# M611B.net
KiCad netlist of a schematic drawn in EAGLE
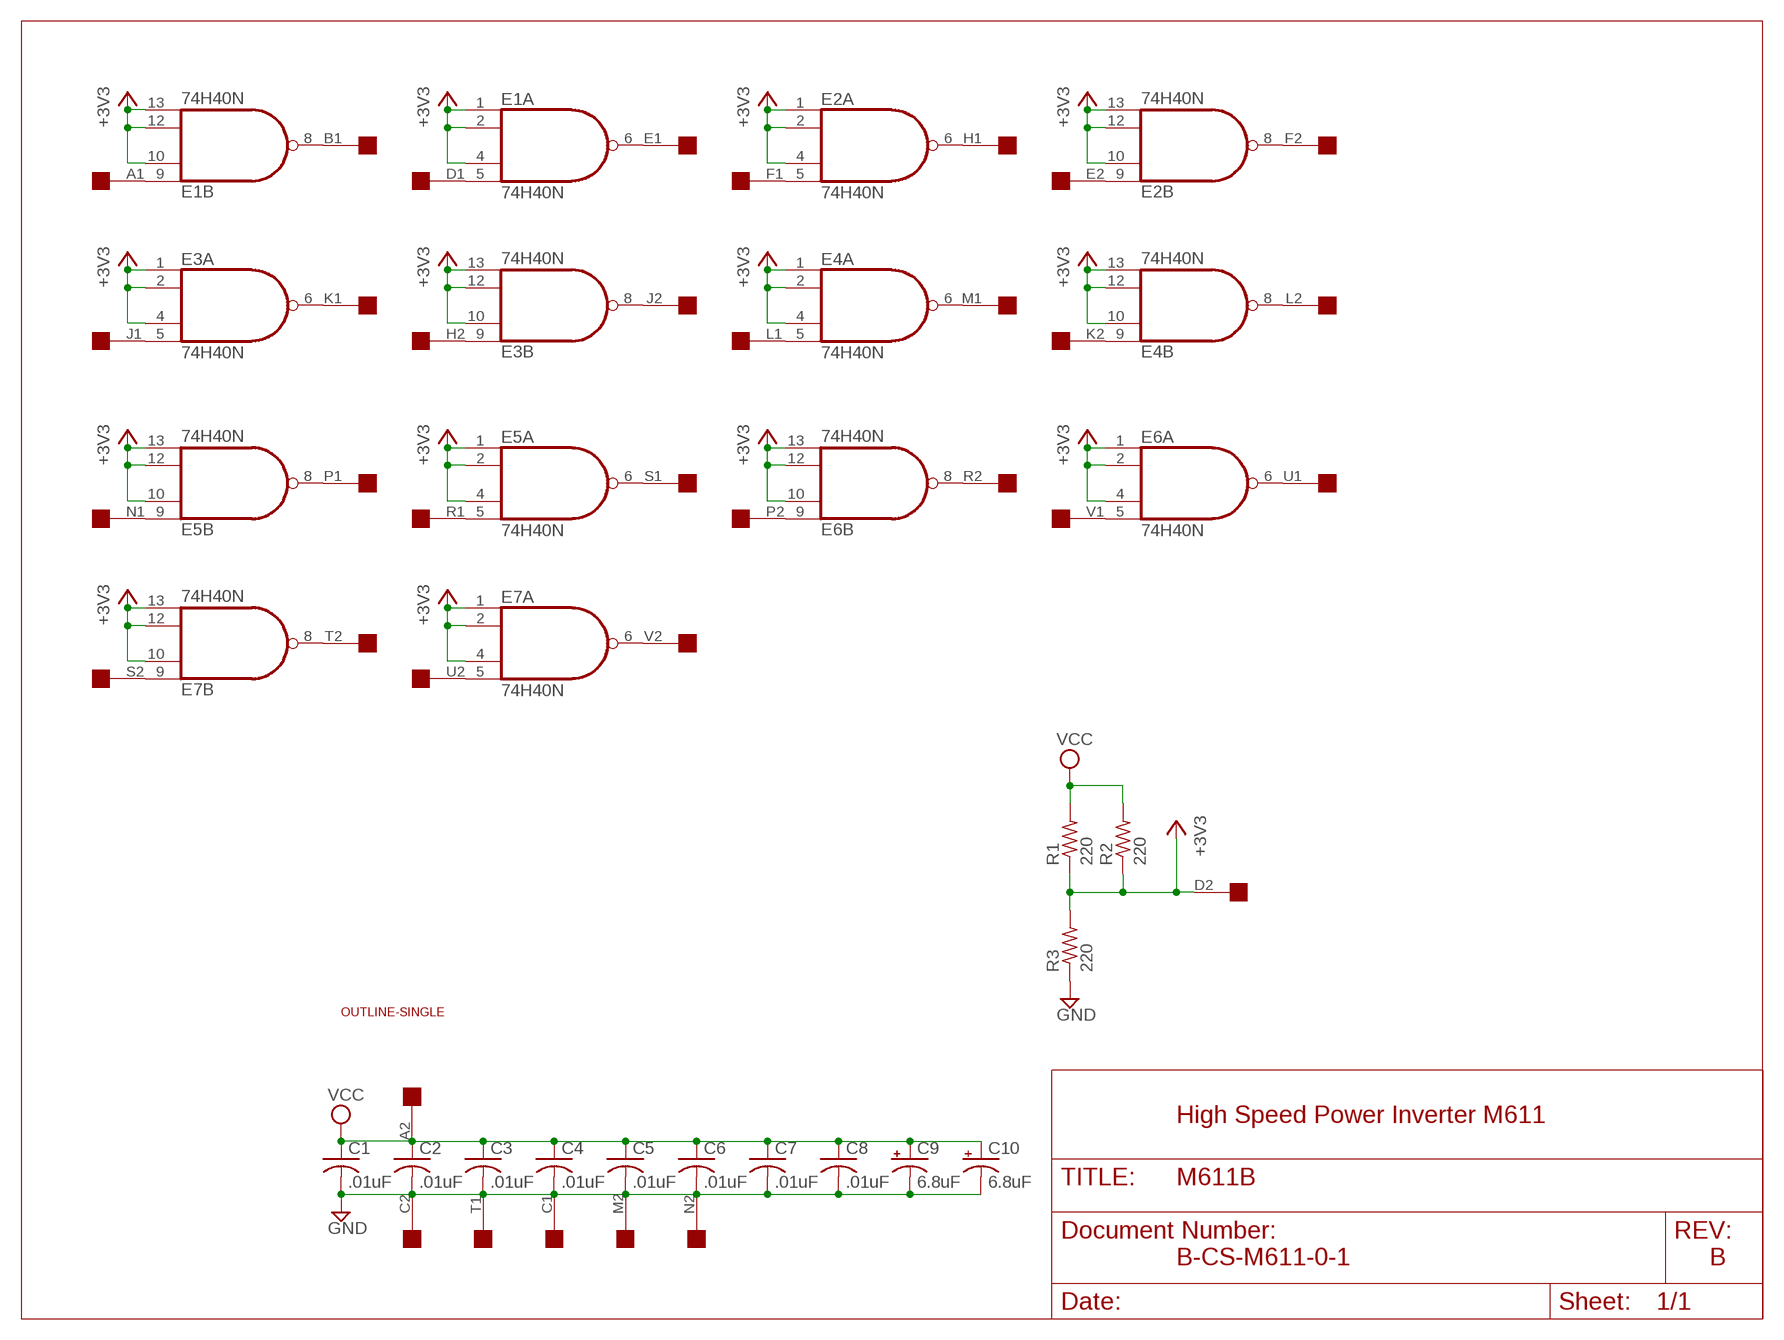
[diagram p0: schematic, sheet 1]

(export (version "E")
  (design (tool "Eeschema 10.0.6"))
  (components
    (comp (ref "C1")
      (value ".01uF")
      (footprint "eagle-import:C050-025X075")
      (libsource (lib "eagle-import") (part "C-US050-025X075"))
    )
    (comp (ref "C2")
      (value ".01uF")
      (footprint "eagle-import:C050-025X075")
      (libsource (lib "eagle-import") (part "C-US050-025X075"))
    )
    (comp (ref "C3")
      (value ".01uF")
      (footprint "eagle-import:C050-025X075")
      (libsource (lib "eagle-import") (part "C-US050-025X075"))
    )
    (comp (ref "C4")
      (value ".01uF")
      (footprint "eagle-import:C050-025X075")
      (libsource (lib "eagle-import") (part "C-US050-025X075"))
    )
    (comp (ref "C5")
      (value ".01uF")
      (footprint "eagle-import:C050-025X075")
      (libsource (lib "eagle-import") (part "C-US050-025X075"))
    )
    (comp (ref "C6")
      (value ".01uF")
      (footprint "eagle-import:C050-025X075")
      (libsource (lib "eagle-import") (part "C-US050-025X075"))
    )
    (comp (ref "C7")
      (value ".01uF")
      (footprint "eagle-import:C050-025X075")
      (libsource (lib "eagle-import") (part "C-US050-025X075"))
    )
    (comp (ref "C8")
      (value ".01uF")
      (footprint "eagle-import:C050-025X075")
      (libsource (lib "eagle-import") (part "C-US050-025X075"))
    )
    (comp (ref "C9")
      (value "6.8uF")
      (footprint "eagle-import:E12-8")
      (libsource (lib "eagle-import") (part "CPOL-USE20-8AXIAL"))
    )
    (comp (ref "C10")
      (value "6.8uF")
      (footprint "eagle-import:E12-8")
      (libsource (lib "eagle-import") (part "CPOL-USE20-8AXIAL"))
    )
    (comp (ref "E1")
      (value "74H40N")
      (footprint "eagle-import:DIL14")
      (libsource (lib "eagle-import") (part "7420NS"))
    )
    (comp (ref "E2")
      (value "74H40N")
      (footprint "eagle-import:DIL14")
      (libsource (lib "eagle-import") (part "7420NS"))
    )
    (comp (ref "E3")
      (value "74H40N")
      (footprint "eagle-import:DIL14")
      (libsource (lib "eagle-import") (part "7420NS"))
    )
    (comp (ref "E4")
      (value "74H40N")
      (footprint "eagle-import:DIL14")
      (libsource (lib "eagle-import") (part "7420NS"))
    )
    (comp (ref "E5")
      (value "74H40N")
      (footprint "eagle-import:DIL14")
      (libsource (lib "eagle-import") (part "7420NS"))
    )
    (comp (ref "E6")
      (value "74H40N")
      (footprint "eagle-import:DIL14")
      (libsource (lib "eagle-import") (part "7420NS"))
    )
    (comp (ref "E7")
      (value "74H40N")
      (footprint "eagle-import:DIL14")
      (libsource (lib "eagle-import") (part "7420NS"))
    )
    (comp (ref "R1")
      (value "220")
      (footprint "eagle-import:0207_10")
      (libsource (lib "eagle-import") (part "R-US_0207/10"))
    )
    (comp (ref "R2")
      (value "220")
      (footprint "eagle-import:0207_10")
      (libsource (lib "eagle-import") (part "R-US_0207/10"))
    )
    (comp (ref "R3")
      (value "220")
      (footprint "eagle-import:0207_10")
      (libsource (lib "eagle-import") (part "R-US_0207/10"))
    )
    (comp (ref "U$1")
      (value "SINGLE")
      (footprint "eagle-import:EDGE-CON2")
      (libsource (lib "eagle-import") (part "SINGLE"))
    )
    (comp (ref "U$4")
      (value "OUTLINE-SINGLE")
      (footprint "eagle-import:SINGLE")
      (libsource (lib "eagle-import") (part "OUTLINE-SINGLE"))
    )
  )
  (nets
    (net (code "1") (name "+3V3") (class "Default")
      (node (ref "E1") (pin "1") (pinfunction "I0_1") (pintype "input"))
      (node (ref "E1") (pin "10") (pinfunction "I1_10") (pintype "input"))
      (node (ref "E1") (pin "12") (pinfunction "I2_12") (pintype "input"))
      (node (ref "E1") (pin "13") (pinfunction "I3_13") (pintype "input"))
      (node (ref "E1") (pin "2") (pinfunction "I1_2") (pintype "input"))
      (node (ref "E1") (pin "4") (pinfunction "I2_4") (pintype "input"))
      (node (ref "E2") (pin "1") (pinfunction "I0_1") (pintype "input"))
      (node (ref "E2") (pin "10") (pinfunction "I1_10") (pintype "input"))
      (node (ref "E2") (pin "12") (pinfunction "I2_12") (pintype "input"))
      (node (ref "E2") (pin "13") (pinfunction "I3_13") (pintype "input"))
      (node (ref "E2") (pin "2") (pinfunction "I1_2") (pintype "input"))
      (node (ref "E2") (pin "4") (pinfunction "I2_4") (pintype "input"))
      (node (ref "E3") (pin "1") (pinfunction "I0_1") (pintype "input"))
      (node (ref "E3") (pin "10") (pinfunction "I1_10") (pintype "input"))
      (node (ref "E3") (pin "12") (pinfunction "I2_12") (pintype "input"))
      (node (ref "E3") (pin "13") (pinfunction "I3_13") (pintype "input"))
      (node (ref "E3") (pin "2") (pinfunction "I1_2") (pintype "input"))
      (node (ref "E3") (pin "4") (pinfunction "I2_4") (pintype "input"))
      (node (ref "E4") (pin "1") (pinfunction "I0_1") (pintype "input"))
      (node (ref "E4") (pin "10") (pinfunction "I1_10") (pintype "input"))
      (node (ref "E4") (pin "12") (pinfunction "I2_12") (pintype "input"))
      (node (ref "E4") (pin "13") (pinfunction "I3_13") (pintype "input"))
      (node (ref "E4") (pin "2") (pinfunction "I1_2") (pintype "input"))
      (node (ref "E4") (pin "4") (pinfunction "I2_4") (pintype "input"))
      (node (ref "E5") (pin "1") (pinfunction "I0_1") (pintype "input"))
      (node (ref "E5") (pin "10") (pinfunction "I1_10") (pintype "input"))
      (node (ref "E5") (pin "12") (pinfunction "I2_12") (pintype "input"))
      (node (ref "E5") (pin "13") (pinfunction "I3_13") (pintype "input"))
      (node (ref "E5") (pin "2") (pinfunction "I1_2") (pintype "input"))
      (node (ref "E5") (pin "4") (pinfunction "I2_4") (pintype "input"))
      (node (ref "E6") (pin "1") (pinfunction "I0_1") (pintype "input"))
      (node (ref "E6") (pin "10") (pinfunction "I1_10") (pintype "input"))
      (node (ref "E6") (pin "12") (pinfunction "I2_12") (pintype "input"))
      (node (ref "E6") (pin "13") (pinfunction "I3_13") (pintype "input"))
      (node (ref "E6") (pin "2") (pinfunction "I1_2") (pintype "input"))
      (node (ref "E6") (pin "4") (pinfunction "I2_4") (pintype "input"))
      (node (ref "E7") (pin "1") (pinfunction "I0_1") (pintype "input"))
      (node (ref "E7") (pin "10") (pinfunction "I1_10") (pintype "input"))
      (node (ref "E7") (pin "12") (pinfunction "I2_12") (pintype "input"))
      (node (ref "E7") (pin "13") (pinfunction "I3_13") (pintype "input"))
      (node (ref "E7") (pin "2") (pinfunction "I1_2") (pintype "input"))
      (node (ref "E7") (pin "4") (pinfunction "I2_4") (pintype "input"))
      (node (ref "R1") (pin "1") (pinfunction "1_1") (pintype "passive"))
      (node (ref "R2") (pin "1") (pinfunction "1_1") (pintype "passive"))
      (node (ref "R3") (pin "2") (pinfunction "2_2") (pintype "passive"))
      (node (ref "U$1") (pin "D2") (pinfunction "1_D2") (pintype "bidirectional"))
    )
    (net (code "2") (name "GND") (class "Default")
      (node (ref "C1") (pin "2") (pinfunction "2_2") (pintype "passive"))
      (node (ref "C10") (pin "-") (pinfunction "-_-") (pintype "passive"))
      (node (ref "C2") (pin "2") (pinfunction "2_2") (pintype "passive"))
      (node (ref "C3") (pin "2") (pinfunction "2_2") (pintype "passive"))
      (node (ref "C4") (pin "2") (pinfunction "2_2") (pintype "passive"))
      (node (ref "C5") (pin "2") (pinfunction "2_2") (pintype "passive"))
      (node (ref "C6") (pin "2") (pinfunction "2_2") (pintype "passive"))
      (node (ref "C7") (pin "2") (pinfunction "2_2") (pintype "passive"))
      (node (ref "C8") (pin "2") (pinfunction "2_2") (pintype "passive"))
      (node (ref "C9") (pin "-") (pinfunction "-_-") (pintype "passive"))
      (node (ref "R3") (pin "1") (pinfunction "1_1") (pintype "passive"))
      (node (ref "U$1") (pin "C1") (pinfunction "1_C1") (pintype "bidirectional"))
      (node (ref "U$1") (pin "C2") (pinfunction "1_C2") (pintype "bidirectional"))
      (node (ref "U$1") (pin "M2") (pinfunction "1_M2") (pintype "bidirectional"))
      (node (ref "U$1") (pin "N2") (pinfunction "1_N2") (pintype "bidirectional"))
      (node (ref "U$1") (pin "T1") (pinfunction "1_T1") (pintype "bidirectional"))
    )
    (net (code "3") (name "Net-(E1A-I3)") (class "Default")
      (node (ref "E1") (pin "5") (pinfunction "I3_5") (pintype "input"))
      (node (ref "U$1") (pin "D1") (pinfunction "1_D1") (pintype "bidirectional"))
    )
    (net (code "4") (name "Net-(E1A-O)") (class "Default")
      (node (ref "E1") (pin "6") (pinfunction "O_6") (pintype "output"))
      (node (ref "U$1") (pin "E1") (pinfunction "1_E1") (pintype "bidirectional"))
    )
    (net (code "5") (name "Net-(E1B-I0)") (class "Default")
      (node (ref "E1") (pin "9") (pinfunction "I0_9") (pintype "input"))
      (node (ref "U$1") (pin "A1") (pinfunction "1_A1") (pintype "bidirectional"))
    )
    (net (code "6") (name "Net-(E1B-O)") (class "Default")
      (node (ref "E1") (pin "8") (pinfunction "O_8") (pintype "output"))
      (node (ref "U$1") (pin "B1") (pinfunction "1_B1") (pintype "bidirectional"))
    )
    (net (code "7") (name "Net-(E2A-I3)") (class "Default")
      (node (ref "E2") (pin "5") (pinfunction "I3_5") (pintype "input"))
      (node (ref "U$1") (pin "F1") (pinfunction "1_F1") (pintype "bidirectional"))
    )
    (net (code "8") (name "Net-(E2A-O)") (class "Default")
      (node (ref "E2") (pin "6") (pinfunction "O_6") (pintype "output"))
      (node (ref "U$1") (pin "H1") (pinfunction "1_H1") (pintype "bidirectional"))
    )
    (net (code "9") (name "Net-(E2B-I0)") (class "Default")
      (node (ref "E2") (pin "9") (pinfunction "I0_9") (pintype "input"))
      (node (ref "U$1") (pin "E2") (pinfunction "1_E2") (pintype "bidirectional"))
    )
    (net (code "10") (name "Net-(E2B-O)") (class "Default")
      (node (ref "E2") (pin "8") (pinfunction "O_8") (pintype "output"))
      (node (ref "U$1") (pin "F2") (pinfunction "1_F2") (pintype "bidirectional"))
    )
    (net (code "11") (name "Net-(E3A-I3)") (class "Default")
      (node (ref "E3") (pin "5") (pinfunction "I3_5") (pintype "input"))
      (node (ref "U$1") (pin "J1") (pinfunction "1_J1") (pintype "bidirectional"))
    )
    (net (code "12") (name "Net-(E3A-O)") (class "Default")
      (node (ref "E3") (pin "6") (pinfunction "O_6") (pintype "output"))
      (node (ref "U$1") (pin "K1") (pinfunction "1_K1") (pintype "bidirectional"))
    )
    (net (code "13") (name "Net-(E3B-I0)") (class "Default")
      (node (ref "E3") (pin "9") (pinfunction "I0_9") (pintype "input"))
      (node (ref "U$1") (pin "H2") (pinfunction "1_H2") (pintype "bidirectional"))
    )
    (net (code "14") (name "Net-(E3B-O)") (class "Default")
      (node (ref "E3") (pin "8") (pinfunction "O_8") (pintype "output"))
      (node (ref "U$1") (pin "J2") (pinfunction "1_J2") (pintype "bidirectional"))
    )
    (net (code "15") (name "Net-(E4A-I3)") (class "Default")
      (node (ref "E4") (pin "5") (pinfunction "I3_5") (pintype "input"))
      (node (ref "U$1") (pin "L1") (pinfunction "1_L1") (pintype "bidirectional"))
    )
    (net (code "16") (name "Net-(E4A-O)") (class "Default")
      (node (ref "E4") (pin "6") (pinfunction "O_6") (pintype "output"))
      (node (ref "U$1") (pin "M1") (pinfunction "1_M1") (pintype "bidirectional"))
    )
    (net (code "17") (name "Net-(E4B-I0)") (class "Default")
      (node (ref "E4") (pin "9") (pinfunction "I0_9") (pintype "input"))
      (node (ref "U$1") (pin "K2") (pinfunction "1_K2") (pintype "bidirectional"))
    )
    (net (code "18") (name "Net-(E4B-O)") (class "Default")
      (node (ref "E4") (pin "8") (pinfunction "O_8") (pintype "output"))
      (node (ref "U$1") (pin "L2") (pinfunction "1_L2") (pintype "bidirectional"))
    )
    (net (code "19") (name "Net-(E5A-I3)") (class "Default")
      (node (ref "E5") (pin "5") (pinfunction "I3_5") (pintype "input"))
      (node (ref "U$1") (pin "R1") (pinfunction "1_R1") (pintype "bidirectional"))
    )
    (net (code "20") (name "Net-(E5A-O)") (class "Default")
      (node (ref "E5") (pin "6") (pinfunction "O_6") (pintype "output"))
      (node (ref "U$1") (pin "S1") (pinfunction "1_S1") (pintype "bidirectional"))
    )
    (net (code "21") (name "Net-(E5B-I0)") (class "Default")
      (node (ref "E5") (pin "9") (pinfunction "I0_9") (pintype "input"))
      (node (ref "U$1") (pin "N1") (pinfunction "1_N1") (pintype "bidirectional"))
    )
    (net (code "22") (name "Net-(E5B-O)") (class "Default")
      (node (ref "E5") (pin "8") (pinfunction "O_8") (pintype "output"))
      (node (ref "U$1") (pin "P1") (pinfunction "1_P1") (pintype "bidirectional"))
    )
    (net (code "23") (name "Net-(E6A-I3)") (class "Default")
      (node (ref "E6") (pin "5") (pinfunction "I3_5") (pintype "input"))
      (node (ref "U$1") (pin "V1") (pinfunction "1_V1") (pintype "bidirectional"))
    )
    (net (code "24") (name "Net-(E6A-O)") (class "Default")
      (node (ref "E6") (pin "6") (pinfunction "O_6") (pintype "output"))
      (node (ref "U$1") (pin "U1") (pinfunction "1_U1") (pintype "bidirectional"))
    )
    (net (code "25") (name "Net-(E6B-I0)") (class "Default")
      (node (ref "E6") (pin "9") (pinfunction "I0_9") (pintype "input"))
      (node (ref "U$1") (pin "P2") (pinfunction "1_P2") (pintype "bidirectional"))
    )
    (net (code "26") (name "Net-(E6B-O)") (class "Default")
      (node (ref "E6") (pin "8") (pinfunction "O_8") (pintype "output"))
      (node (ref "U$1") (pin "R2") (pinfunction "1_R2") (pintype "bidirectional"))
    )
    (net (code "27") (name "Net-(E7A-I3)") (class "Default")
      (node (ref "E7") (pin "5") (pinfunction "I3_5") (pintype "input"))
      (node (ref "U$1") (pin "U2") (pinfunction "1_U2") (pintype "bidirectional"))
    )
    (net (code "28") (name "Net-(E7A-O)") (class "Default")
      (node (ref "E7") (pin "6") (pinfunction "O_6") (pintype "output"))
      (node (ref "U$1") (pin "V2") (pinfunction "1_V2") (pintype "bidirectional"))
    )
    (net (code "29") (name "Net-(E7B-I0)") (class "Default")
      (node (ref "E7") (pin "9") (pinfunction "I0_9") (pintype "input"))
      (node (ref "U$1") (pin "S2") (pinfunction "1_S2") (pintype "bidirectional"))
    )
    (net (code "30") (name "Net-(E7B-O)") (class "Default")
      (node (ref "E7") (pin "8") (pinfunction "O_8") (pintype "output"))
      (node (ref "U$1") (pin "T2") (pinfunction "1_T2") (pintype "bidirectional"))
    )
    (net (code "31") (name "VCC") (class "Default")
      (node (ref "C1") (pin "1") (pinfunction "1_1") (pintype "passive"))
      (node (ref "C10") (pin "+") (pinfunction "+_+") (pintype "passive"))
      (node (ref "C2") (pin "1") (pinfunction "1_1") (pintype "passive"))
      (node (ref "C3") (pin "1") (pinfunction "1_1") (pintype "passive"))
      (node (ref "C4") (pin "1") (pinfunction "1_1") (pintype "passive"))
      (node (ref "C5") (pin "1") (pinfunction "1_1") (pintype "passive"))
      (node (ref "C6") (pin "1") (pinfunction "1_1") (pintype "passive"))
      (node (ref "C7") (pin "1") (pinfunction "1_1") (pintype "passive"))
      (node (ref "C8") (pin "1") (pinfunction "1_1") (pintype "passive"))
      (node (ref "C9") (pin "+") (pinfunction "+_+") (pintype "passive"))
      (node (ref "R1") (pin "2") (pinfunction "2_2") (pintype "passive"))
      (node (ref "R2") (pin "2") (pinfunction "2_2") (pintype "passive"))
      (node (ref "U$1") (pin "A2") (pinfunction "1_A2") (pintype "bidirectional"))
    )
  )
)
